# Sheet1.net
KiCad netlist of a schematic drawn in Altium Designer
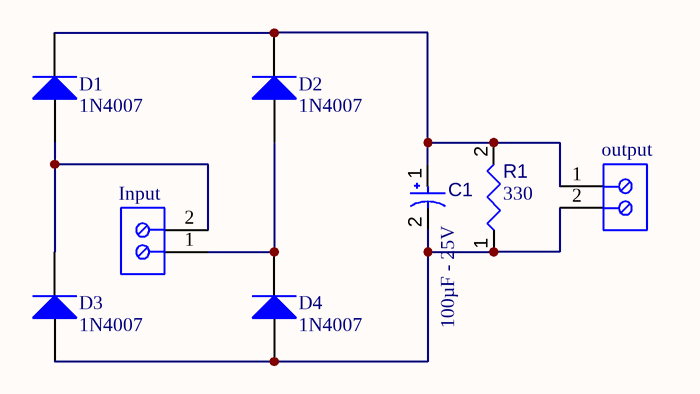
[diagram p0: Sheet1.SchDoc]

(export (version "E")
  (design (tool "Eeschema 10.0.6"))
  (components
    (comp (ref "C1")
      (value "100µF - 25V")
      (footprint "CAPPR55-250-1120X630X1220")
      (description "Aluminum Electrolytic Capacitor, 22 uF, +/- 20%, 100 V, -40 to 85 degC, 2-Pin THD, RoHS, Bulk")
      (fields (field (name "MANUFACTURER") "Panasonic") (field (name "TOLERANCE") "20%"))
      (libsource (lib "Alexandria University") (part "CAP-P-2"))
    )
    (comp (ref "D1")
      (value "1N4007")
      (footprint "FAIR-DO-41-2")
      (description "General Purpose Rectifier, 1.1 V, 1.0 A, -55 to 175 degC, 2-Pin DO-41, RoHS, Tape and Reel")
      (fields (field (name "MANUFACTURER") "Fairchild"))
      (libsource (lib "Alexandria University") (part "KESE-D_K1A2-2"))
    )
    (comp (ref "D2")
      (value "1N4007")
      (footprint "FAIR-DO-41-2")
      (description "General Purpose Rectifier, 1.1 V, 1.0 A, -55 to 175 degC, 2-Pin DO-41, RoHS, Tape and Reel")
      (fields (field (name "MANUFACTURER") "Fairchild"))
      (libsource (lib "Alexandria University") (part "KESE-D_K1A2-2"))
    )
    (comp (ref "D3")
      (value "1N4007")
      (footprint "FAIR-DO-41-2")
      (description "General Purpose Rectifier, 1.1 V, 1.0 A, -55 to 175 degC, 2-Pin DO-41, RoHS, Tape and Reel")
      (fields (field (name "MANUFACTURER") "Fairchild"))
      (libsource (lib "Alexandria University") (part "KESE-D_K1A2-2"))
    )
    (comp (ref "D4")
      (value "1N4007")
      (footprint "FAIR-DO-41-2")
      (description "General Purpose Rectifier, 1.1 V, 1.0 A, -55 to 175 degC, 2-Pin DO-41, RoHS, Tape and Reel")
      (fields (field (name "MANUFACTURER") "Fairchild"))
      (libsource (lib "Alexandria University") (part "KESE-D_K1A2-2"))
    )
    (comp (ref "Input")
      (value "691137710002")
      (footprint "terminals")
      (description "Series 1377 - 5.00 mm Horizontal Entry with Pressure Clamp WR-TBL, 2 pin")
      (fields (field (name "MANUFACTURER") "Wurth Elektronik") (field (name "PUBLISHER") "WurthElektronik"))
      (libsource (lib "Schlib1") (part "terminals"))
    )
    (comp (ref "output")
      (value "691137710002")
      (footprint "terminals")
      (description "Series 1377 - 5.00 mm Horizontal Entry with Pressure Clamp WR-TBL, 2 pin")
      (fields (field (name "MANUFACTURER") "Wurth Elektronik") (field (name "PUBLISHER") "WurthElektronik"))
      (libsource (lib "Schlib1") (part "terminals"))
    )
    (comp (ref "R1")
      (value "330")
      (footprint "RESA60-630X240")
      (description "Axial Resistor, 221 Ohm, +/- 1%, 250 mW, -55 to 155 degC, 2-Pin THD, RoHS, Bulk")
      (fields (field (name "POWER") "250mW") (field (name "TOLERANCE") "1%"))
      (libsource (lib "Alexandria University") (part "RES-2"))
    )
  )
  (nets
    (net (code "1") (name "Net-(D1-A)") (class "Default")
      (node (ref "D1") (pin "2") (pinfunction "A_2") (pintype "passive"))
      (node (ref "D3") (pin "1") (pinfunction "K_1") (pintype "passive"))
      (node (ref "Input") (pin "2") (pinfunction "2_2") (pintype "passive"))
    )
    (net (code "2") (name "Net-(D1-K)") (class "Default")
      (node (ref "C1") (pin "1") (pinfunction "1_1") (pintype "passive"))
      (node (ref "D1") (pin "1") (pinfunction "K_1") (pintype "passive"))
      (node (ref "D2") (pin "1") (pinfunction "K_1") (pintype "passive"))
      (node (ref "R1") (pin "2") (pinfunction "2_2") (pintype "passive"))
      (node (ref "output") (pin "1") (pinfunction "1_1") (pintype "passive"))
    )
    (net (code "3") (name "Net-(D2-A)") (class "Default")
      (node (ref "D2") (pin "2") (pinfunction "A_2") (pintype "passive"))
      (node (ref "D4") (pin "1") (pinfunction "K_1") (pintype "passive"))
      (node (ref "Input") (pin "1") (pinfunction "1_1") (pintype "passive"))
    )
    (net (code "4") (name "Net-(D3-A)") (class "Default")
      (node (ref "C1") (pin "2") (pinfunction "2_2") (pintype "passive"))
      (node (ref "D3") (pin "2") (pinfunction "A_2") (pintype "passive"))
      (node (ref "D4") (pin "2") (pinfunction "A_2") (pintype "passive"))
      (node (ref "R1") (pin "1") (pinfunction "1_1") (pintype "passive"))
      (node (ref "output") (pin "2") (pinfunction "2_2") (pintype "passive"))
    )
  )
)
